# statuum.net
KiCad netlist of a schematic drawn in EAGLE
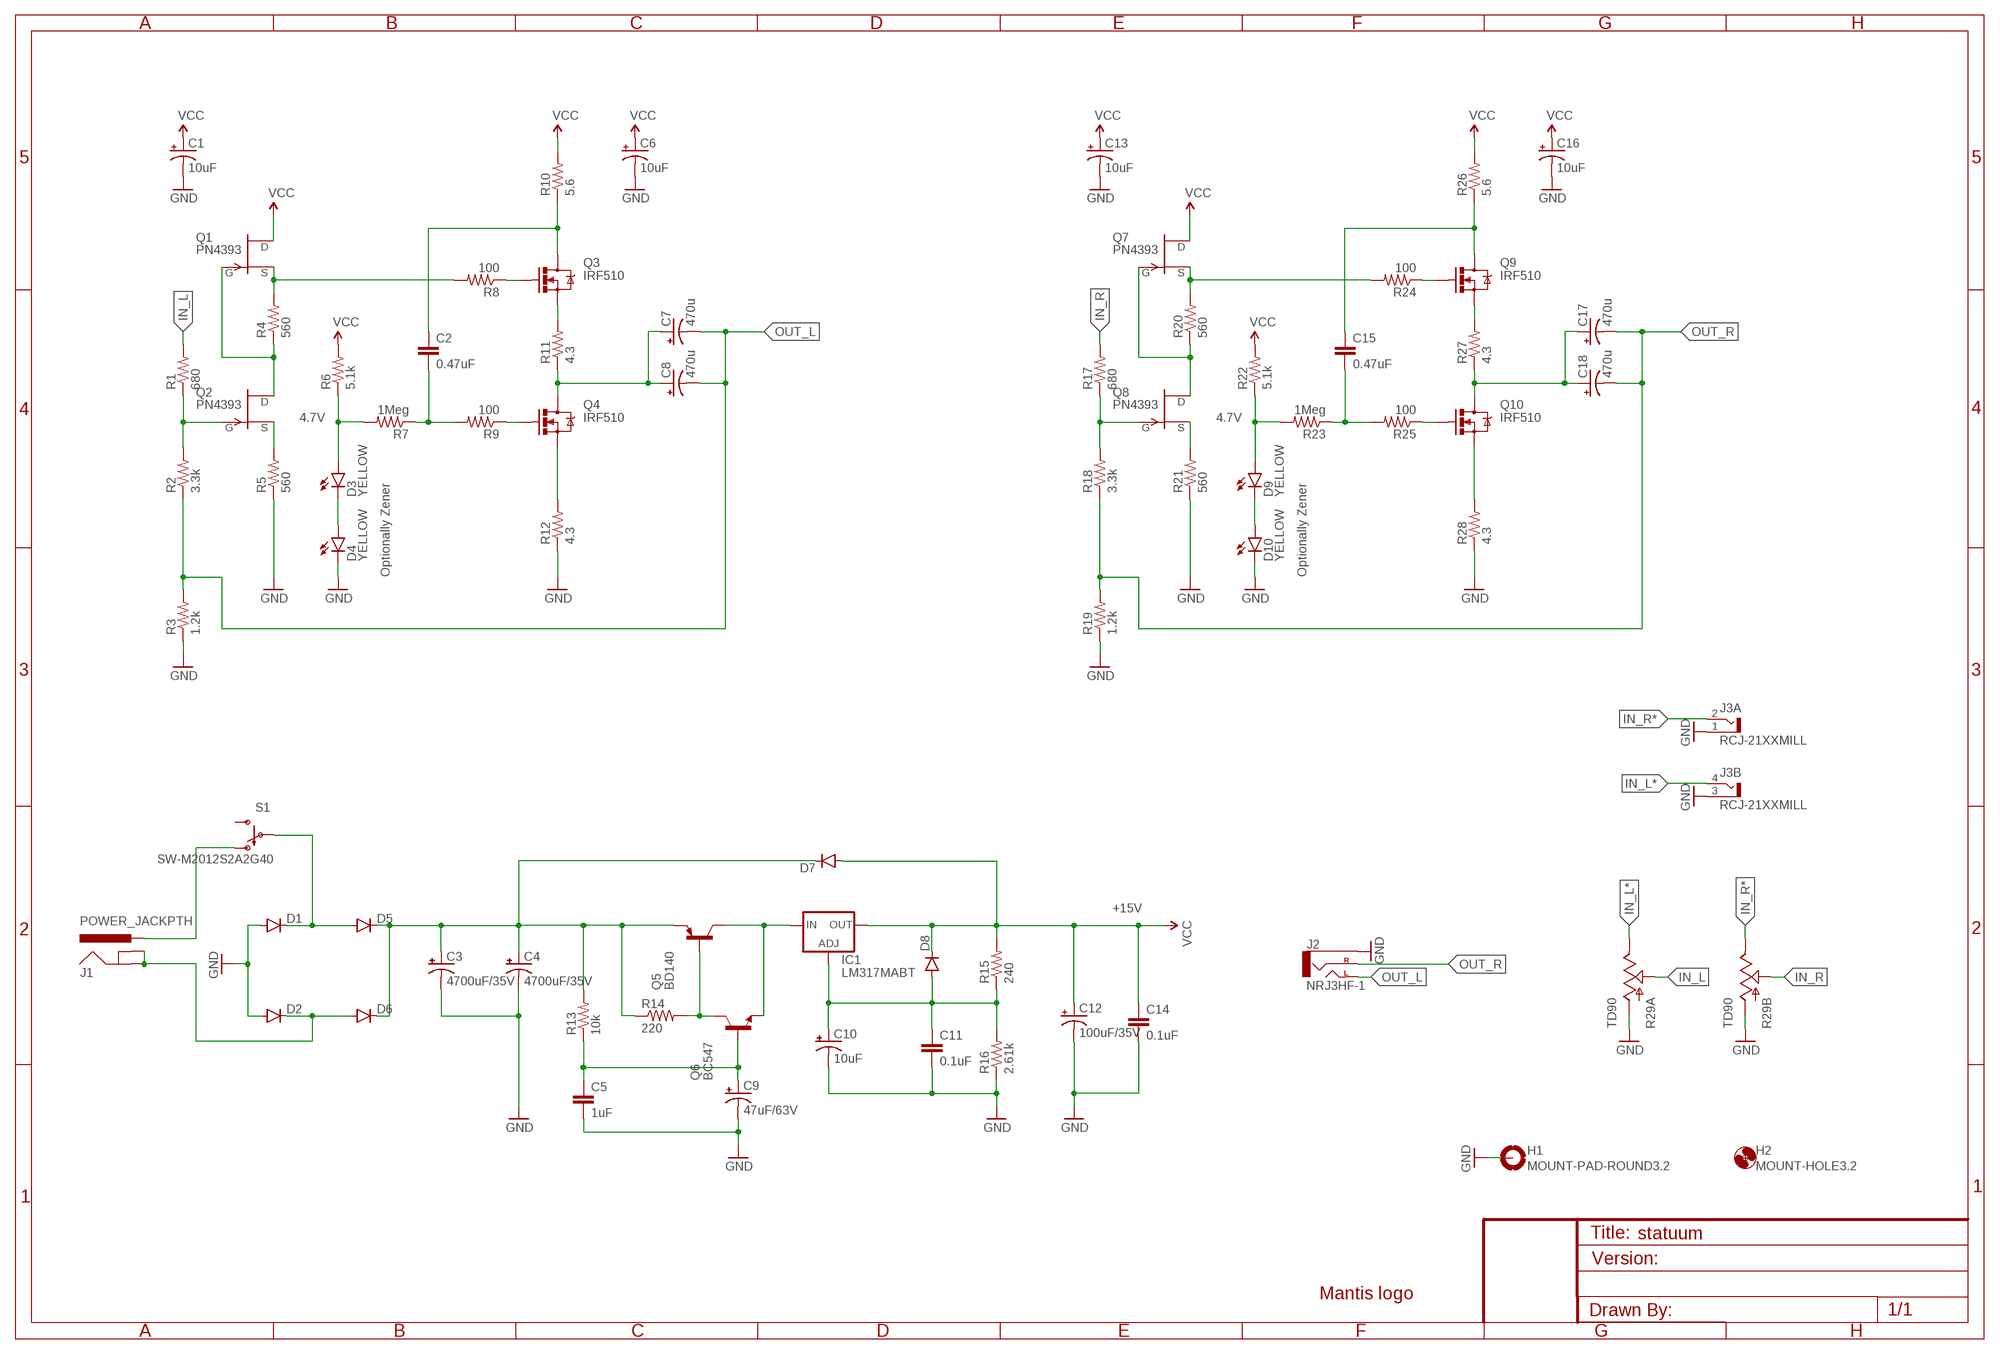
[diagram p0: schematic, sheet 1]

(export (version "E")
  (design (tool "Eeschema 10.0.6"))
  (components
    (comp (ref "C1")
      (value "10uF")
      (footprint "eagle-import:CPOL-RADIAL-5_2.5-SM")
      (libsource (lib "eagle-import") (part "CAP_POLPTH-5/2.5-SM"))
    )
    (comp (ref "C2")
      (value "0.47uF")
      (footprint "eagle-import:C5B3.5")
      (libsource (lib "eagle-import") (part "C5/3.5"))
    )
    (comp (ref "C3")
      (value "4700uF/35V")
      (footprint "eagle-import:CPOL-RADIAL-16_7.5")
      (libsource (lib "eagle-import") (part "CAP_POLPTH-16/7.5"))
    )
    (comp (ref "C4")
      (value "4700uF/35V")
      (footprint "eagle-import:CPOL-RADIAL-16_7.5")
      (libsource (lib "eagle-import") (part "CAP_POLPTH-16/7.5"))
    )
    (comp (ref "C5")
      (value "1uF")
      (footprint "eagle-import:CAP-PTH-SMALL")
      (libsource (lib "eagle-import") (part "CAPPTH"))
    )
    (comp (ref "C6")
      (value "10uF")
      (footprint "eagle-import:CPOL-RADIAL-5_2.5-SM")
      (libsource (lib "eagle-import") (part "CAP_POLPTH-5/2.5-SM"))
    )
    (comp (ref "C7")
      (value "470u")
      (footprint "eagle-import:CPOL-RADIAL-8_3.5")
      (libsource (lib "eagle-import") (part "CAP_POLPTH-8/3.5"))
    )
    (comp (ref "C8")
      (value "470u")
      (footprint "eagle-import:CPOL-RADIAL-8_3.5")
      (libsource (lib "eagle-import") (part "CAP_POLPTH-8/3.5"))
    )
    (comp (ref "C9")
      (value "47uF/63V")
      (footprint "eagle-import:CPOL-RADIAL-6.5_2.5")
      (libsource (lib "eagle-import") (part "CAP_POLPTH-6.5/2.5"))
    )
    (comp (ref "C10")
      (value "10uF")
      (footprint "eagle-import:CPOL-RADIAL-5_2.5-SM")
      (libsource (lib "eagle-import") (part "CAP_POLPTH-5/2.5-SM"))
    )
    (comp (ref "C11")
      (value "0.1uF")
      (footprint "eagle-import:CAP-PTH-SMALL")
      (libsource (lib "eagle-import") (part "CAPPTH"))
    )
    (comp (ref "C12")
      (value "100uF/35V")
      (footprint "eagle-import:CPOL-RADIAL-8_3.5")
      (libsource (lib "eagle-import") (part "CAP_POLPTH-8/3.5"))
    )
    (comp (ref "C13")
      (value "10uF")
      (footprint "eagle-import:CPOL-RADIAL-5_2.5-SM")
      (libsource (lib "eagle-import") (part "CAP_POLPTH-5/2.5-SM"))
    )
    (comp (ref "C14")
      (value "0.1uF")
      (footprint "eagle-import:CAP-PTH-SMALL")
      (libsource (lib "eagle-import") (part "CAPPTH"))
    )
    (comp (ref "C15")
      (value "0.47uF")
      (footprint "eagle-import:C5B3.5")
      (libsource (lib "eagle-import") (part "C5/3.5"))
    )
    (comp (ref "C16")
      (value "10uF")
      (footprint "eagle-import:CPOL-RADIAL-5_2.5-SM")
      (libsource (lib "eagle-import") (part "CAP_POLPTH-5/2.5-SM"))
    )
    (comp (ref "C17")
      (value "470u")
      (footprint "eagle-import:CPOL-RADIAL-8_3.5")
      (libsource (lib "eagle-import") (part "CAP_POLPTH-8/3.5"))
    )
    (comp (ref "C18")
      (value "470u")
      (footprint "eagle-import:CPOL-RADIAL-8_3.5")
      (libsource (lib "eagle-import") (part "CAP_POLPTH-8/3.5"))
    )
    (comp (ref "D1")
      (value "DIODEPTH")
      (footprint "eagle-import:DIODE-1N4001")
      (libsource (lib "eagle-import") (part "DIODEPTH"))
    )
    (comp (ref "D2")
      (value "DIODEPTH")
      (footprint "eagle-import:DIODE-1N4001")
      (libsource (lib "eagle-import") (part "DIODEPTH"))
    )
    (comp (ref "D3")
      (value "YELLOW")
      (footprint "eagle-import:LED3MM-SM")
      (libsource (lib "eagle-import") (part "LED3MM-SM"))
    )
    (comp (ref "D4")
      (value "YELLOW")
      (footprint "eagle-import:LED3MM-SM")
      (libsource (lib "eagle-import") (part "LED3MM-SM"))
    )
    (comp (ref "D5")
      (value "DIODEPTH")
      (footprint "eagle-import:DIODE-1N4001")
      (libsource (lib "eagle-import") (part "DIODEPTH"))
    )
    (comp (ref "D6")
      (value "DIODEPTH")
      (footprint "eagle-import:DIODE-1N4001")
      (libsource (lib "eagle-import") (part "DIODEPTH"))
    )
    (comp (ref "D7")
      (value "DIODEPTH")
      (footprint "eagle-import:DIODE-1N4001")
      (libsource (lib "eagle-import") (part "DIODEPTH"))
    )
    (comp (ref "D8")
      (value "DIODEPTH")
      (footprint "eagle-import:DIODE-1N4001")
      (libsource (lib "eagle-import") (part "DIODEPTH"))
    )
    (comp (ref "D9")
      (value "YELLOW")
      (footprint "eagle-import:LED3MM-SM")
      (libsource (lib "eagle-import") (part "LED3MM-SM"))
    )
    (comp (ref "D10")
      (value "YELLOW")
      (footprint "eagle-import:LED3MM-SM")
      (libsource (lib "eagle-import") (part "LED3MM-SM"))
    )
    (comp (ref "H1")
      (value "MOUNT-PAD-ROUND3.2")
      (footprint "eagle-import:3,2-PAD")
      (libsource (lib "eagle-import") (part "MOUNT-PAD-ROUND3.2"))
    )
    (comp (ref "H2")
      (value "MOUNT-HOLE3.2")
      (footprint "eagle-import:3,2")
      (libsource (lib "eagle-import") (part "MOUNT-HOLE3.2"))
    )
    (comp (ref "IC1")
      (value "LM317MABT")
      (footprint "eagle-import:TO220L1")
      (libsource (lib "eagle-import") (part "LM317?MABT"))
    )
    (comp (ref "J1")
      (value "POWER_JACKPTH")
      (footprint "eagle-import:POWER_JACK_PTH")
      (libsource (lib "eagle-import") (part "POWER_JACKPTH"))
    )
    (comp (ref "J2")
      (value "NRJ3HF-1")
      (footprint "eagle-import:NRJ3HF")
      (libsource (lib "eagle-import") (part "NRJ3HF-1"))
    )
    (comp (ref "J3")
      (value "RCJ-21XXMILL")
      (footprint "eagle-import:RCJ-21-MILL")
      (libsource (lib "eagle-import") (part "RCJ-21XXMILL"))
    )
    (comp (ref "LOGO1")
      (value "LOGO-MANTIS")
      (footprint "eagle-import:LOGO-MANTIS")
      (libsource (lib "eagle-import") (part "LOGO-MANTIS"))
    )
    (comp (ref "Q1")
      (value "PN4393")
      (footprint "eagle-import:TO-92")
      (libsource (lib "eagle-import") (part "PN4393"))
    )
    (comp (ref "Q2")
      (value "PN4393")
      (footprint "eagle-import:TO-92")
      (libsource (lib "eagle-import") (part "PN4393"))
    )
    (comp (ref "Q3")
      (value "IRF510")
      (footprint "eagle-import:TO220-HORIZ")
      (libsource (lib "eagle-import") (part "IRF510"))
    )
    (comp (ref "Q4")
      (value "IRF510")
      (footprint "eagle-import:TO220-HORIZ")
      (libsource (lib "eagle-import") (part "IRF510"))
    )
    (comp (ref "Q5")
      (value "BD140")
      (footprint "eagle-import:TO126")
      (libsource (lib "eagle-import") (part "BD140"))
    )
    (comp (ref "Q6")
      (value "BC547")
      (footprint "eagle-import:TO-92")
      (libsource (lib "eagle-import") (part "BC547"))
    )
    (comp (ref "Q7")
      (value "PN4393")
      (footprint "eagle-import:TO-92")
      (libsource (lib "eagle-import") (part "PN4393"))
    )
    (comp (ref "Q8")
      (value "PN4393")
      (footprint "eagle-import:TO-92")
      (libsource (lib "eagle-import") (part "PN4393"))
    )
    (comp (ref "Q9")
      (value "IRF510")
      (footprint "eagle-import:TO220-HORIZ")
      (libsource (lib "eagle-import") (part "IRF510"))
    )
    (comp (ref "Q10")
      (value "IRF510")
      (footprint "eagle-import:TO220-HORIZ")
      (libsource (lib "eagle-import") (part "IRF510"))
    )
    (comp (ref "R1")
      (value "680")
      (footprint "eagle-import:AXIAL-0.4")
      (libsource (lib "eagle-import") (part "RESISTORPTH-1/4W"))
    )
    (comp (ref "R2")
      (value "3.3k")
      (footprint "eagle-import:AXIAL-0.4")
      (libsource (lib "eagle-import") (part "RESISTORPTH-1/4W"))
    )
    (comp (ref "R3")
      (value "1.2k")
      (footprint "eagle-import:AXIAL-0.4")
      (libsource (lib "eagle-import") (part "RESISTORPTH-1/4W"))
    )
    (comp (ref "R4")
      (value "560")
      (footprint "eagle-import:AXIAL-0.4")
      (libsource (lib "eagle-import") (part "RESISTORPTH-1/4W"))
    )
    (comp (ref "R5")
      (value "560")
      (footprint "eagle-import:AXIAL-0.4")
      (libsource (lib "eagle-import") (part "RESISTORPTH-1/4W"))
    )
    (comp (ref "R6")
      (value "5.1k")
      (footprint "eagle-import:AXIAL-0.4")
      (libsource (lib "eagle-import") (part "RESISTORPTH-1/4W"))
    )
    (comp (ref "R7")
      (value "1Meg")
      (footprint "eagle-import:AXIAL-0.4")
      (libsource (lib "eagle-import") (part "RESISTORPTH-1/4W"))
    )
    (comp (ref "R8")
      (value "100")
      (footprint "eagle-import:AXIAL-0.4")
      (libsource (lib "eagle-import") (part "RESISTORPTH-1/4W"))
    )
    (comp (ref "R9")
      (value "100")
      (footprint "eagle-import:AXIAL-0.4")
      (libsource (lib "eagle-import") (part "RESISTORPTH-1/4W"))
    )
    (comp (ref "R10")
      (value "5.6")
      (footprint "eagle-import:AXIAL-0.4")
      (libsource (lib "eagle-import") (part "RESISTORPTH-1/4W"))
    )
    (comp (ref "R11")
      (value "4.3")
      (footprint "eagle-import:AXIAL-0.4")
      (libsource (lib "eagle-import") (part "RESISTORPTH-1/4W"))
    )
    (comp (ref "R12")
      (value "4.3")
      (footprint "eagle-import:AXIAL-0.4")
      (libsource (lib "eagle-import") (part "RESISTORPTH-1/4W"))
    )
    (comp (ref "R13")
      (value "10k")
      (footprint "eagle-import:AXIAL-0.4")
      (libsource (lib "eagle-import") (part "RESISTORPTH-1/4W"))
    )
    (comp (ref "R14")
      (value "220")
      (footprint "eagle-import:AXIAL-0.4")
      (libsource (lib "eagle-import") (part "RESISTORPTH-1/4W"))
    )
    (comp (ref "R15")
      (value "240")
      (footprint "eagle-import:AXIAL-0.4")
      (libsource (lib "eagle-import") (part "RESISTORPTH-1/4W"))
    )
    (comp (ref "R16")
      (value "2.61k")
      (footprint "eagle-import:AXIAL-0.4")
      (libsource (lib "eagle-import") (part "RESISTORPTH-1/4W"))
    )
    (comp (ref "R17")
      (value "680")
      (footprint "eagle-import:AXIAL-0.4")
      (libsource (lib "eagle-import") (part "RESISTORPTH-1/4W"))
    )
    (comp (ref "R18")
      (value "3.3k")
      (footprint "eagle-import:AXIAL-0.4")
      (libsource (lib "eagle-import") (part "RESISTORPTH-1/4W"))
    )
    (comp (ref "R19")
      (value "1.2k")
      (footprint "eagle-import:AXIAL-0.4")
      (libsource (lib "eagle-import") (part "RESISTORPTH-1/4W"))
    )
    (comp (ref "R20")
      (value "560")
      (footprint "eagle-import:AXIAL-0.4")
      (libsource (lib "eagle-import") (part "RESISTORPTH-1/4W"))
    )
    (comp (ref "R21")
      (value "560")
      (footprint "eagle-import:AXIAL-0.4")
      (libsource (lib "eagle-import") (part "RESISTORPTH-1/4W"))
    )
    (comp (ref "R22")
      (value "5.1k")
      (footprint "eagle-import:AXIAL-0.4")
      (libsource (lib "eagle-import") (part "RESISTORPTH-1/4W"))
    )
    (comp (ref "R23")
      (value "1Meg")
      (footprint "eagle-import:AXIAL-0.4")
      (libsource (lib "eagle-import") (part "RESISTORPTH-1/4W"))
    )
    (comp (ref "R24")
      (value "100")
      (footprint "eagle-import:AXIAL-0.4")
      (libsource (lib "eagle-import") (part "RESISTORPTH-1/4W"))
    )
    (comp (ref "R25")
      (value "100")
      (footprint "eagle-import:AXIAL-0.4")
      (libsource (lib "eagle-import") (part "RESISTORPTH-1/4W"))
    )
    (comp (ref "R26")
      (value "5.6")
      (footprint "eagle-import:AXIAL-0.4")
      (libsource (lib "eagle-import") (part "RESISTORPTH-1/4W"))
    )
    (comp (ref "R27")
      (value "4.3")
      (footprint "eagle-import:AXIAL-0.4")
      (libsource (lib "eagle-import") (part "RESISTORPTH-1/4W"))
    )
    (comp (ref "R28")
      (value "4.3")
      (footprint "eagle-import:AXIAL-0.4")
      (libsource (lib "eagle-import") (part "RESISTORPTH-1/4W"))
    )
    (comp (ref "R29")
      (value "TD90")
      (footprint "eagle-import:PTD902")
      (libsource (lib "eagle-import") (part "TD90"))
    )
    (comp (ref "S1")
      (value "SW-M2012S2A2G40")
      (footprint "eagle-import:SW-M2012S2A2G40")
      (libsource (lib "eagle-import") (part "SW-M2012S2A2G40"))
    )
  )
  (nets
    (net (code "1") (name "GND") (class "Default")
      (node (ref "C1") (pin "2") (pinfunction "-_2") (pintype "passive"))
      (node (ref "C10") (pin "2") (pinfunction "-_2") (pintype "passive"))
      (node (ref "C11") (pin "2") (pinfunction "2_2") (pintype "passive"))
      (node (ref "C12") (pin "2") (pinfunction "-_2") (pintype "passive"))
      (node (ref "C13") (pin "2") (pinfunction "-_2") (pintype "passive"))
      (node (ref "C14") (pin "2") (pinfunction "2_2") (pintype "passive"))
      (node (ref "C16") (pin "2") (pinfunction "-_2") (pintype "passive"))
      (node (ref "C3") (pin "2") (pinfunction "-_2") (pintype "passive"))
      (node (ref "C4") (pin "2") (pinfunction "-_2") (pintype "passive"))
      (node (ref "C5") (pin "2") (pinfunction "2_2") (pintype "passive"))
      (node (ref "C6") (pin "2") (pinfunction "-_2") (pintype "passive"))
      (node (ref "C9") (pin "2") (pinfunction "-_2") (pintype "passive"))
      (node (ref "D1") (pin "A") (pinfunction "A_A") (pintype "passive"))
      (node (ref "D10") (pin "K") (pinfunction "C_K") (pintype "passive"))
      (node (ref "D2") (pin "A") (pinfunction "A_A") (pintype "passive"))
      (node (ref "D4") (pin "K") (pinfunction "C_K") (pintype "passive"))
      (node (ref "H1") (pin "B3,2") (pinfunction "MOUNT_B3,2") (pintype "passive"))
      (node (ref "J2") (pin "S") (pinfunction "SLEEVE_S") (pintype "bidirectional"))
      (node (ref "J3") (pin "1") (pinfunction "S_1") (pintype "passive"))
      (node (ref "J3") (pin "3") (pinfunction "S_3") (pintype "passive"))
      (node (ref "R12") (pin "P$1") (pinfunction "1_P$1") (pintype "passive"))
      (node (ref "R16") (pin "P$1") (pinfunction "1_P$1") (pintype "passive"))
      (node (ref "R19") (pin "P$1") (pinfunction "1_P$1") (pintype "passive"))
      (node (ref "R21") (pin "P$1") (pinfunction "1_P$1") (pintype "passive"))
      (node (ref "R28") (pin "P$1") (pinfunction "1_P$1") (pintype "passive"))
      (node (ref "R29") (pin "R1.1") (pinfunction "A_R1.1") (pintype "passive"))
      (node (ref "R29") (pin "R2.1") (pinfunction "A_R2.1") (pintype "passive"))
      (node (ref "R3") (pin "P$1") (pinfunction "1_P$1") (pintype "passive"))
      (node (ref "R5") (pin "P$1") (pinfunction "1_P$1") (pintype "passive"))
    )
    (net (code "2") (name "IN_L") (class "Default")
      (node (ref "R1") (pin "P$2") (pinfunction "2_P$2") (pintype "passive"))
      (node (ref "R29") (pin "R1.2") (pinfunction "S_R1.2") (pintype "passive"))
    )
    (net (code "3") (name "IN_L*") (class "Default")
      (node (ref "J3") (pin "4") (pinfunction "T_4") (pintype "passive"))
      (node (ref "R29") (pin "R1.3") (pinfunction "E_R1.3") (pintype "passive"))
    )
    (net (code "4") (name "IN_R") (class "Default")
      (node (ref "R17") (pin "P$2") (pinfunction "2_P$2") (pintype "passive"))
      (node (ref "R29") (pin "R2.2") (pinfunction "S_R2.2") (pintype "passive"))
    )
    (net (code "5") (name "IN_R*") (class "Default")
      (node (ref "J3") (pin "2") (pinfunction "T_2") (pintype "passive"))
      (node (ref "R29") (pin "R2.3") (pinfunction "E_R2.3") (pintype "passive"))
    )
    (net (code "6") (name "Net-(C3-+)") (class "Default")
      (node (ref "C3") (pin "1") (pinfunction "+_1") (pintype "passive"))
      (node (ref "C4") (pin "1") (pinfunction "+_1") (pintype "passive"))
      (node (ref "D5") (pin "C") (pinfunction "C_C") (pintype "passive"))
      (node (ref "D6") (pin "C") (pinfunction "C_C") (pintype "passive"))
      (node (ref "D7") (pin "C") (pinfunction "C_C") (pintype "passive"))
      (node (ref "Q5") (pin "1") (pinfunction "E_1") (pintype "passive"))
      (node (ref "R13") (pin "P$2") (pinfunction "2_P$2") (pintype "passive"))
      (node (ref "R14") (pin "P$1") (pinfunction "1_P$1") (pintype "passive"))
    )
    (net (code "7") (name "Net-(C7-+)") (class "Default")
      (node (ref "C7") (pin "1") (pinfunction "+_1") (pintype "passive"))
      (node (ref "C8") (pin "1") (pinfunction "+_1") (pintype "passive"))
      (node (ref "Q4") (pin "2") (pinfunction "D_2") (pintype "passive"))
      (node (ref "R11") (pin "P$1") (pinfunction "1_P$1") (pintype "passive"))
    )
    (net (code "8") (name "Net-(C9-+)") (class "Default")
      (node (ref "C5") (pin "1") (pinfunction "1_1") (pintype "passive"))
      (node (ref "C9") (pin "1") (pinfunction "+_1") (pintype "passive"))
      (node (ref "Q6") (pin "2") (pinfunction "B_2") (pintype "passive"))
      (node (ref "R13") (pin "P$1") (pinfunction "1_P$1") (pintype "passive"))
    )
    (net (code "9") (name "Net-(C10-+)") (class "Default")
      (node (ref "C10") (pin "1") (pinfunction "+_1") (pintype "passive"))
      (node (ref "C11") (pin "1") (pinfunction "1_1") (pintype "passive"))
      (node (ref "D8") (pin "A") (pinfunction "A_A") (pintype "passive"))
      (node (ref "IC1") (pin "1") (pinfunction "ADJ_1") (pintype "input"))
      (node (ref "R15") (pin "P$1") (pinfunction "1_P$1") (pintype "passive"))
      (node (ref "R16") (pin "P$2") (pinfunction "2_P$2") (pintype "passive"))
    )
    (net (code "10") (name "Net-(C17-+)") (class "Default")
      (node (ref "C17") (pin "1") (pinfunction "+_1") (pintype "passive"))
      (node (ref "C18") (pin "1") (pinfunction "+_1") (pintype "passive"))
      (node (ref "Q10") (pin "2") (pinfunction "D_2") (pintype "passive"))
      (node (ref "R27") (pin "P$1") (pinfunction "1_P$1") (pintype "passive"))
    )
    (net (code "11") (name "Net-(D2-PadC)") (class "Default")
      (node (ref "D2") (pin "C") (pinfunction "C_C") (pintype "passive"))
      (node (ref "D6") (pin "A") (pinfunction "A_A") (pintype "passive"))
      (node (ref "J1") (pin "GND") (pinfunction "GND_GND") (pintype "bidirectional"))
      (node (ref "J1") (pin "GNDBREAK") (pinfunction "GNDBREAK_GNDBREAK") (pintype "bidirectional"))
    )
    (net (code "12") (name "Net-(D3-C)") (class "Default")
      (node (ref "D3") (pin "K") (pinfunction "C_K") (pintype "passive"))
      (node (ref "D4") (pin "A") (pinfunction "A_A") (pintype "passive"))
    )
    (net (code "13") (name "Net-(D9-C)") (class "Default")
      (node (ref "D10") (pin "A") (pinfunction "A_A") (pintype "passive"))
      (node (ref "D9") (pin "K") (pinfunction "C_K") (pintype "passive"))
    )
    (net (code "14") (name "Net-(IC1-IN)") (class "Default")
      (node (ref "IC1") (pin "3") (pinfunction "IN_3") (pintype "input"))
      (node (ref "Q5") (pin "2") (pinfunction "C_2") (pintype "passive"))
      (node (ref "Q6") (pin "3") (pinfunction "E_3") (pintype "passive"))
    )
    (net (code "15") (name "Net-(Q1-G)") (class "Default")
      (node (ref "Q1") (pin "3") (pinfunction "G_3") (pintype "passive"))
      (node (ref "Q2") (pin "1") (pinfunction "D_1") (pintype "passive"))
      (node (ref "R4") (pin "P$1") (pinfunction "1_P$1") (pintype "passive"))
    )
    (net (code "16") (name "Net-(Q1-S)") (class "Default")
      (node (ref "Q1") (pin "2") (pinfunction "S_2") (pintype "passive"))
      (node (ref "R4") (pin "P$2") (pinfunction "2_P$2") (pintype "passive"))
      (node (ref "R8") (pin "P$2") (pinfunction "2_P$2") (pintype "passive"))
    )
    (net (code "17") (name "Net-(Q2-G)") (class "Default")
      (node (ref "Q2") (pin "3") (pinfunction "G_3") (pintype "passive"))
      (node (ref "R1") (pin "P$1") (pinfunction "1_P$1") (pintype "passive"))
      (node (ref "R2") (pin "P$2") (pinfunction "2_P$2") (pintype "passive"))
    )
    (net (code "18") (name "Net-(Q2-S)") (class "Default")
      (node (ref "Q2") (pin "2") (pinfunction "S_2") (pintype "passive"))
      (node (ref "R5") (pin "P$2") (pinfunction "2_P$2") (pintype "passive"))
    )
    (net (code "19") (name "Net-(Q3-D)") (class "Default")
      (node (ref "C2") (pin "1") (pinfunction "1_1") (pintype "passive"))
      (node (ref "Q3") (pin "2") (pinfunction "D_2") (pintype "passive"))
      (node (ref "R10") (pin "P$1") (pinfunction "1_P$1") (pintype "passive"))
    )
    (net (code "20") (name "Net-(Q3-G)") (class "Default")
      (node (ref "Q3") (pin "1") (pinfunction "G_1") (pintype "passive"))
      (node (ref "R8") (pin "P$1") (pinfunction "1_P$1") (pintype "passive"))
    )
    (net (code "21") (name "Net-(Q3-S)") (class "Default")
      (node (ref "Q3") (pin "3") (pinfunction "S_3") (pintype "passive"))
      (node (ref "R11") (pin "P$2") (pinfunction "2_P$2") (pintype "passive"))
    )
    (net (code "22") (name "Net-(Q4-G)") (class "Default")
      (node (ref "Q4") (pin "1") (pinfunction "G_1") (pintype "passive"))
      (node (ref "R9") (pin "P$1") (pinfunction "1_P$1") (pintype "passive"))
    )
    (net (code "23") (name "Net-(Q4-S)") (class "Default")
      (node (ref "Q4") (pin "3") (pinfunction "S_3") (pintype "passive"))
      (node (ref "R12") (pin "P$2") (pinfunction "2_P$2") (pintype "passive"))
    )
    (net (code "24") (name "Net-(Q5-B)") (class "Default")
      (node (ref "Q5") (pin "3") (pinfunction "B_3") (pintype "passive"))
      (node (ref "Q6") (pin "1") (pinfunction "C_1") (pintype "passive"))
      (node (ref "R14") (pin "P$2") (pinfunction "2_P$2") (pintype "passive"))
    )
    (net (code "25") (name "Net-(Q7-G)") (class "Default")
      (node (ref "Q7") (pin "3") (pinfunction "G_3") (pintype "passive"))
      (node (ref "Q8") (pin "1") (pinfunction "D_1") (pintype "passive"))
      (node (ref "R20") (pin "P$1") (pinfunction "1_P$1") (pintype "passive"))
    )
    (net (code "26") (name "Net-(Q7-S)") (class "Default")
      (node (ref "Q7") (pin "2") (pinfunction "S_2") (pintype "passive"))
      (node (ref "R20") (pin "P$2") (pinfunction "2_P$2") (pintype "passive"))
      (node (ref "R24") (pin "P$2") (pinfunction "2_P$2") (pintype "passive"))
    )
    (net (code "27") (name "Net-(Q8-G)") (class "Default")
      (node (ref "Q8") (pin "3") (pinfunction "G_3") (pintype "passive"))
      (node (ref "R17") (pin "P$1") (pinfunction "1_P$1") (pintype "passive"))
      (node (ref "R18") (pin "P$2") (pinfunction "2_P$2") (pintype "passive"))
    )
    (net (code "28") (name "Net-(Q8-S)") (class "Default")
      (node (ref "Q8") (pin "2") (pinfunction "S_2") (pintype "passive"))
      (node (ref "R21") (pin "P$2") (pinfunction "2_P$2") (pintype "passive"))
    )
    (net (code "29") (name "Net-(Q9-D)") (class "Default")
      (node (ref "C15") (pin "1") (pinfunction "1_1") (pintype "passive"))
      (node (ref "Q9") (pin "2") (pinfunction "D_2") (pintype "passive"))
      (node (ref "R26") (pin "P$1") (pinfunction "1_P$1") (pintype "passive"))
    )
    (net (code "30") (name "Net-(Q9-G)") (class "Default")
      (node (ref "Q9") (pin "1") (pinfunction "G_1") (pintype "passive"))
      (node (ref "R24") (pin "P$1") (pinfunction "1_P$1") (pintype "passive"))
    )
    (net (code "31") (name "Net-(Q9-S)") (class "Default")
      (node (ref "Q9") (pin "3") (pinfunction "S_3") (pintype "passive"))
      (node (ref "R27") (pin "P$2") (pinfunction "2_P$2") (pintype "passive"))
    )
    (net (code "32") (name "Net-(Q10-G)") (class "Default")
      (node (ref "Q10") (pin "1") (pinfunction "G_1") (pintype "passive"))
      (node (ref "R25") (pin "P$1") (pinfunction "1_P$1") (pintype "passive"))
    )
    (net (code "33") (name "Net-(Q10-S)") (class "Default")
      (node (ref "Q10") (pin "3") (pinfunction "S_3") (pintype "passive"))
      (node (ref "R28") (pin "P$2") (pinfunction "2_P$2") (pintype "passive"))
    )
    (net (code "34") (name "Net-(R6-1)") (class "Default")
      (node (ref "D3") (pin "A") (pinfunction "A_A") (pintype "passive"))
      (node (ref "R6") (pin "P$1") (pinfunction "1_P$1") (pintype "passive"))
      (node (ref "R7") (pin "P$2") (pinfunction "2_P$2") (pintype "passive"))
    )
    (net (code "35") (name "Net-(R7-1)") (class "Default")
      (node (ref "C2") (pin "2") (pinfunction "2_2") (pintype "passive"))
      (node (ref "R7") (pin "P$1") (pinfunction "1_P$1") (pintype "passive"))
      (node (ref "R9") (pin "P$2") (pinfunction "2_P$2") (pintype "passive"))
    )
    (net (code "36") (name "Net-(R22-1)") (class "Default")
      (node (ref "D9") (pin "A") (pinfunction "A_A") (pintype "passive"))
      (node (ref "R22") (pin "P$1") (pinfunction "1_P$1") (pintype "passive"))
      (node (ref "R23") (pin "P$2") (pinfunction "2_P$2") (pintype "passive"))
    )
    (net (code "37") (name "Net-(R23-1)") (class "Default")
      (node (ref "C15") (pin "2") (pinfunction "2_2") (pintype "passive"))
      (node (ref "R23") (pin "P$1") (pinfunction "1_P$1") (pintype "passive"))
      (node (ref "R25") (pin "P$2") (pinfunction "2_P$2") (pintype "passive"))
    )
    (net (code "38") (name "Net-(S1-O)") (class "Default")
      (node (ref "J1") (pin "PWR") (pinfunction "PWR_PWR") (pintype "bidirectional"))
      (node (ref "S1") (pin "UP-CONNECT") (pinfunction "O_UP-CONNECT") (pintype "passive"))
    )
    (net (code "39") (name "Net-(S1-P)") (class "Default")
      (node (ref "D1") (pin "C") (pinfunction "C_C") (pintype "passive"))
      (node (ref "D5") (pin "A") (pinfunction "A_A") (pintype "passive"))
      (node (ref "S1") (pin "S") (pinfunction "P_S") (pintype "passive"))
    )
    (net (code "40") (name "OUT_L") (class "Default")
      (node (ref "C7") (pin "2") (pinfunction "-_2") (pintype "passive"))
      (node (ref "C8") (pin "2") (pinfunction "-_2") (pintype "passive"))
      (node (ref "J2") (pin "T") (pinfunction "LEFT_T") (pintype "bidirectional"))
      (node (ref "R2") (pin "P$1") (pinfunction "1_P$1") (pintype "passive"))
      (node (ref "R3") (pin "P$2") (pinfunction "2_P$2") (pintype "passive"))
    )
    (net (code "41") (name "OUT_R") (class "Default")
      (node (ref "C17") (pin "2") (pinfunction "-_2") (pintype "passive"))
      (node (ref "C18") (pin "2") (pinfunction "-_2") (pintype "passive"))
      (node (ref "J2") (pin "R") (pinfunction "RIGHT_R") (pintype "bidirectional"))
      (node (ref "R18") (pin "P$1") (pinfunction "1_P$1") (pintype "passive"))
      (node (ref "R19") (pin "P$2") (pinfunction "2_P$2") (pintype "passive"))
    )
    (net (code "42") (name "VCC") (class "Default")
      (node (ref "C1") (pin "1") (pinfunction "+_1") (pintype "passive"))
      (node (ref "C12") (pin "1") (pinfunction "+_1") (pintype "passive"))
      (node (ref "C13") (pin "1") (pinfunction "+_1") (pintype "passive"))
      (node (ref "C14") (pin "1") (pinfunction "1_1") (pintype "passive"))
      (node (ref "C16") (pin "1") (pinfunction "+_1") (pintype "passive"))
      (node (ref "C6") (pin "1") (pinfunction "+_1") (pintype "passive"))
      (node (ref "D7") (pin "A") (pinfunction "A_A") (pintype "passive"))
      (node (ref "D8") (pin "C") (pinfunction "C_C") (pintype "passive"))
      (node (ref "IC1") (pin "2") (pinfunction "OUT_2") (pintype "passive"))
      (node (ref "Q1") (pin "1") (pinfunction "D_1") (pintype "passive"))
      (node (ref "Q7") (pin "1") (pinfunction "D_1") (pintype "passive"))
      (node (ref "R10") (pin "P$2") (pinfunction "2_P$2") (pintype "passive"))
      (node (ref "R15") (pin "P$2") (pinfunction "2_P$2") (pintype "passive"))
      (node (ref "R22") (pin "P$2") (pinfunction "2_P$2") (pintype "passive"))
      (node (ref "R26") (pin "P$2") (pinfunction "2_P$2") (pintype "passive"))
      (node (ref "R6") (pin "P$2") (pinfunction "2_P$2") (pintype "passive"))
    )
    (net (code "43") (name "unconnected-(S1-S-PadDN-CONNECT)") (class "Default")
      (node (ref "S1") (pin "DN-CONNECT") (pinfunction "S_DN-CONNECT") (pintype "passive"))
    )
  )
)
